# INA333.net
KiCad netlist of a schematic drawn in Altium Designer
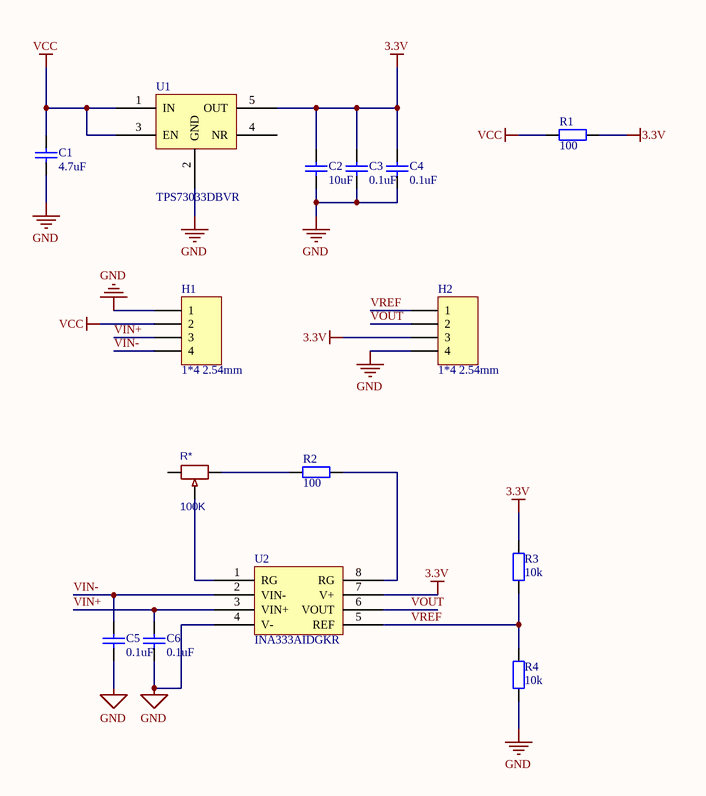
[diagram p0: INA333模块.SchDoc]

(export (version "E")
  (design (tool "Eeschema 10.0.6"))
  (components
    (comp (ref "C1") (value "4.7uF") (footprint "0805_C") (libsource (lib "INA333模块") (part "C_非极性电容")))
    (comp (ref "C2") (value "10uF") (footprint "0805_C") (libsource (lib "INA333模块") (part "C_非极性电容")))
    (comp (ref "C3") (value "0.1uF") (footprint "0805_C") (libsource (lib "INA333模块") (part "C_非极性电容")))
    (comp (ref "C4") (value "0.1uF") (footprint "0805_C") (libsource (lib "INA333模块") (part "C_非极性电容")))
    (comp (ref "C5") (value "0.1uF") (footprint "0805_C") (libsource (lib "INA333模块") (part "C_非极性电容")))
    (comp (ref "C6") (value "0.1uF") (footprint "0805_C") (libsource (lib "INA333模块") (part "C_非极性电容")))
    (comp (ref "H1")
      (value "1*4 2.54mm")
      (footprint "HDR1X4")
      (fields (field (name "PUBLISHER") "Altium Limited"))
      (libsource (lib "INA333模块") (part "1*4 2.54mm"))
    )
    (comp (ref "H2")
      (value "1*4 2.54mm")
      (footprint "HDR1X4")
      (fields (field (name "PUBLISHER") "Altium Limited"))
      (libsource (lib "INA333模块") (part "1*4 2.54mm"))
    )
    (comp (ref "R*")
      (value "100K")
      (footprint "RES-ADJ-TH_3P-L9.5-W4.9-P2.50-L_3296W")
      (fields
        (field (name "BOM_SUPPLIER PART") "C118900")
        (field (name "BOM_MANUFACTURER PART") "3296W-1-100")
        (field (name "CONTRIBUTOR") "LCSC")
      )
      (libsource (lib "INA333模块") (part "R_可调"))
    )
    (comp (ref "R1")
      (value "100")
      (footprint "0805_R")
      (description "贴片电阻")
      (libsource (lib "INA333模块") (part "R"))
    )
    (comp (ref "R2")
      (value "100")
      (footprint "0805_R")
      (description "贴片电阻")
      (libsource (lib "") (part "R_2"))
    )
    (comp (ref "R3")
      (value "10k")
      (footprint "0805_R")
      (description "贴片电阻")
      (libsource (lib "") (part "R_1"))
    )
    (comp (ref "R4")
      (value "10k")
      (footprint "0805_R")
      (description "贴片电阻")
      (libsource (lib "") (part "R_1"))
    )
    (comp (ref "U1")
      (value "TPS73033DBVR")
      (footprint "SOT-23-5")
      (description "SOT23-5")
      (libsource (lib "INA333模块") (part "TPS73033DBVR"))
    )
    (comp (ref "U2")
      (value "INA333AIDGKR")
      (footprint "MSOP-8")
      (description "MSOP-8")
      (libsource (lib "INA333模块") (part "INA333AIDGKR"))
    )
  )
  (nets
    (net (code "1") (name "/VIN+") (class "Default")
      (node (ref "C6") (pin "2") (pinfunction "2_2") (pintype "passive"))
      (node (ref "H1") (pin "3") (pinfunction "3_3") (pintype "passive"))
      (node (ref "U2") (pin "3") (pinfunction "VIN+_3") (pintype "passive"))
    )
    (net (code "2") (name "/VIN-") (class "Default")
      (node (ref "C5") (pin "2") (pinfunction "2_2") (pintype "passive"))
      (node (ref "H1") (pin "4") (pinfunction "4_4") (pintype "passive"))
      (node (ref "U2") (pin "2") (pinfunction "VIN-_2") (pintype "passive"))
    )
    (net (code "3") (name "/VOUT") (class "Default")
      (node (ref "H2") (pin "2") (pinfunction "2_2") (pintype "passive"))
      (node (ref "U2") (pin "6") (pinfunction "VOUT_6") (pintype "passive"))
    )
    (net (code "4") (name "/VREF") (class "Default")
      (node (ref "H2") (pin "1") (pinfunction "1_1") (pintype "passive"))
      (node (ref "R3") (pin "2") (pinfunction "2_2") (pintype "passive"))
      (node (ref "R4") (pin "1") (pinfunction "1_1") (pintype "passive"))
      (node (ref "U2") (pin "5") (pinfunction "REF_5") (pintype "passive"))
    )
    (net (code "5") (name "3.3V") (class "Default")
      (node (ref "C2") (pin "2") (pinfunction "2_2") (pintype "passive"))
      (node (ref "C3") (pin "2") (pinfunction "2_2") (pintype "passive"))
      (node (ref "C4") (pin "2") (pinfunction "2_2") (pintype "passive"))
      (node (ref "H2") (pin "3") (pinfunction "3_3") (pintype "passive"))
      (node (ref "R1") (pin "2") (pinfunction "2_2") (pintype "passive"))
      (node (ref "R3") (pin "1") (pinfunction "1_1") (pintype "passive"))
      (node (ref "U1") (pin "5") (pinfunction "OUT_5") (pintype "passive"))
      (node (ref "U2") (pin "7") (pinfunction "V+_7") (pintype "passive"))
    )
    (net (code "6") (name "GND") (class "Default")
      (node (ref "C1") (pin "1") (pinfunction "1_1") (pintype "passive"))
      (node (ref "C2") (pin "1") (pinfunction "1_1") (pintype "passive"))
      (node (ref "C3") (pin "1") (pinfunction "1_1") (pintype "passive"))
      (node (ref "C4") (pin "1") (pinfunction "1_1") (pintype "passive"))
      (node (ref "C5") (pin "1") (pinfunction "1_1") (pintype "passive"))
      (node (ref "C6") (pin "1") (pinfunction "1_1") (pintype "passive"))
      (node (ref "H1") (pin "1") (pinfunction "1_1") (pintype "passive"))
      (node (ref "H2") (pin "4") (pinfunction "4_4") (pintype "passive"))
      (node (ref "R4") (pin "2") (pinfunction "2_2") (pintype "passive"))
      (node (ref "U1") (pin "2") (pinfunction "GND_2") (pintype "passive"))
      (node (ref "U2") (pin "4") (pinfunction "V-_4") (pintype "passive"))
    )
    (net (code "7") (name "Net-(R*-Pad1)") (class "Default")
      (node (ref "R*") (pin "1") (pinfunction "1_1") (pintype "passive"))
      (node (ref "R2") (pin "2") (pinfunction "2_2") (pintype "passive"))
    )
    (net (code "8") (name "Net-(R*-Pad2)") (class "Default")
      (node (ref "R*") (pin "2") (pinfunction "2_2") (pintype "passive"))
      (node (ref "U2") (pin "1") (pinfunction "RG_1") (pintype "passive"))
    )
    (net (code "9") (name "Net-(R2-Pad1)") (class "Default")
      (node (ref "R2") (pin "1") (pinfunction "1_1") (pintype "passive"))
      (node (ref "U2") (pin "8") (pinfunction "RG_8") (pintype "passive"))
    )
    (net (code "10") (name "VCC") (class "Default")
      (node (ref "C1") (pin "2") (pinfunction "2_2") (pintype "passive"))
      (node (ref "H1") (pin "2") (pinfunction "2_2") (pintype "passive"))
      (node (ref "R1") (pin "1") (pinfunction "1_1") (pintype "passive"))
      (node (ref "U1") (pin "1") (pinfunction "IN_1") (pintype "passive"))
      (node (ref "U1") (pin "3") (pinfunction "EN_3") (pintype "passive"))
    )
    (net (code "11") (name "unconnected-(R*-Pad3)") (class "Default")
      (node (ref "R*") (pin "3") (pinfunction "3_3") (pintype "passive"))
    )
    (net (code "12") (name "unconnected-(U1-NR-Pad4)") (class "Default")
      (node (ref "U1") (pin "4") (pinfunction "NR_4") (pintype "passive"))
    )
  )
)
